# DB3100.net
KiCad netlist of a schematic drawn in Altium Designer
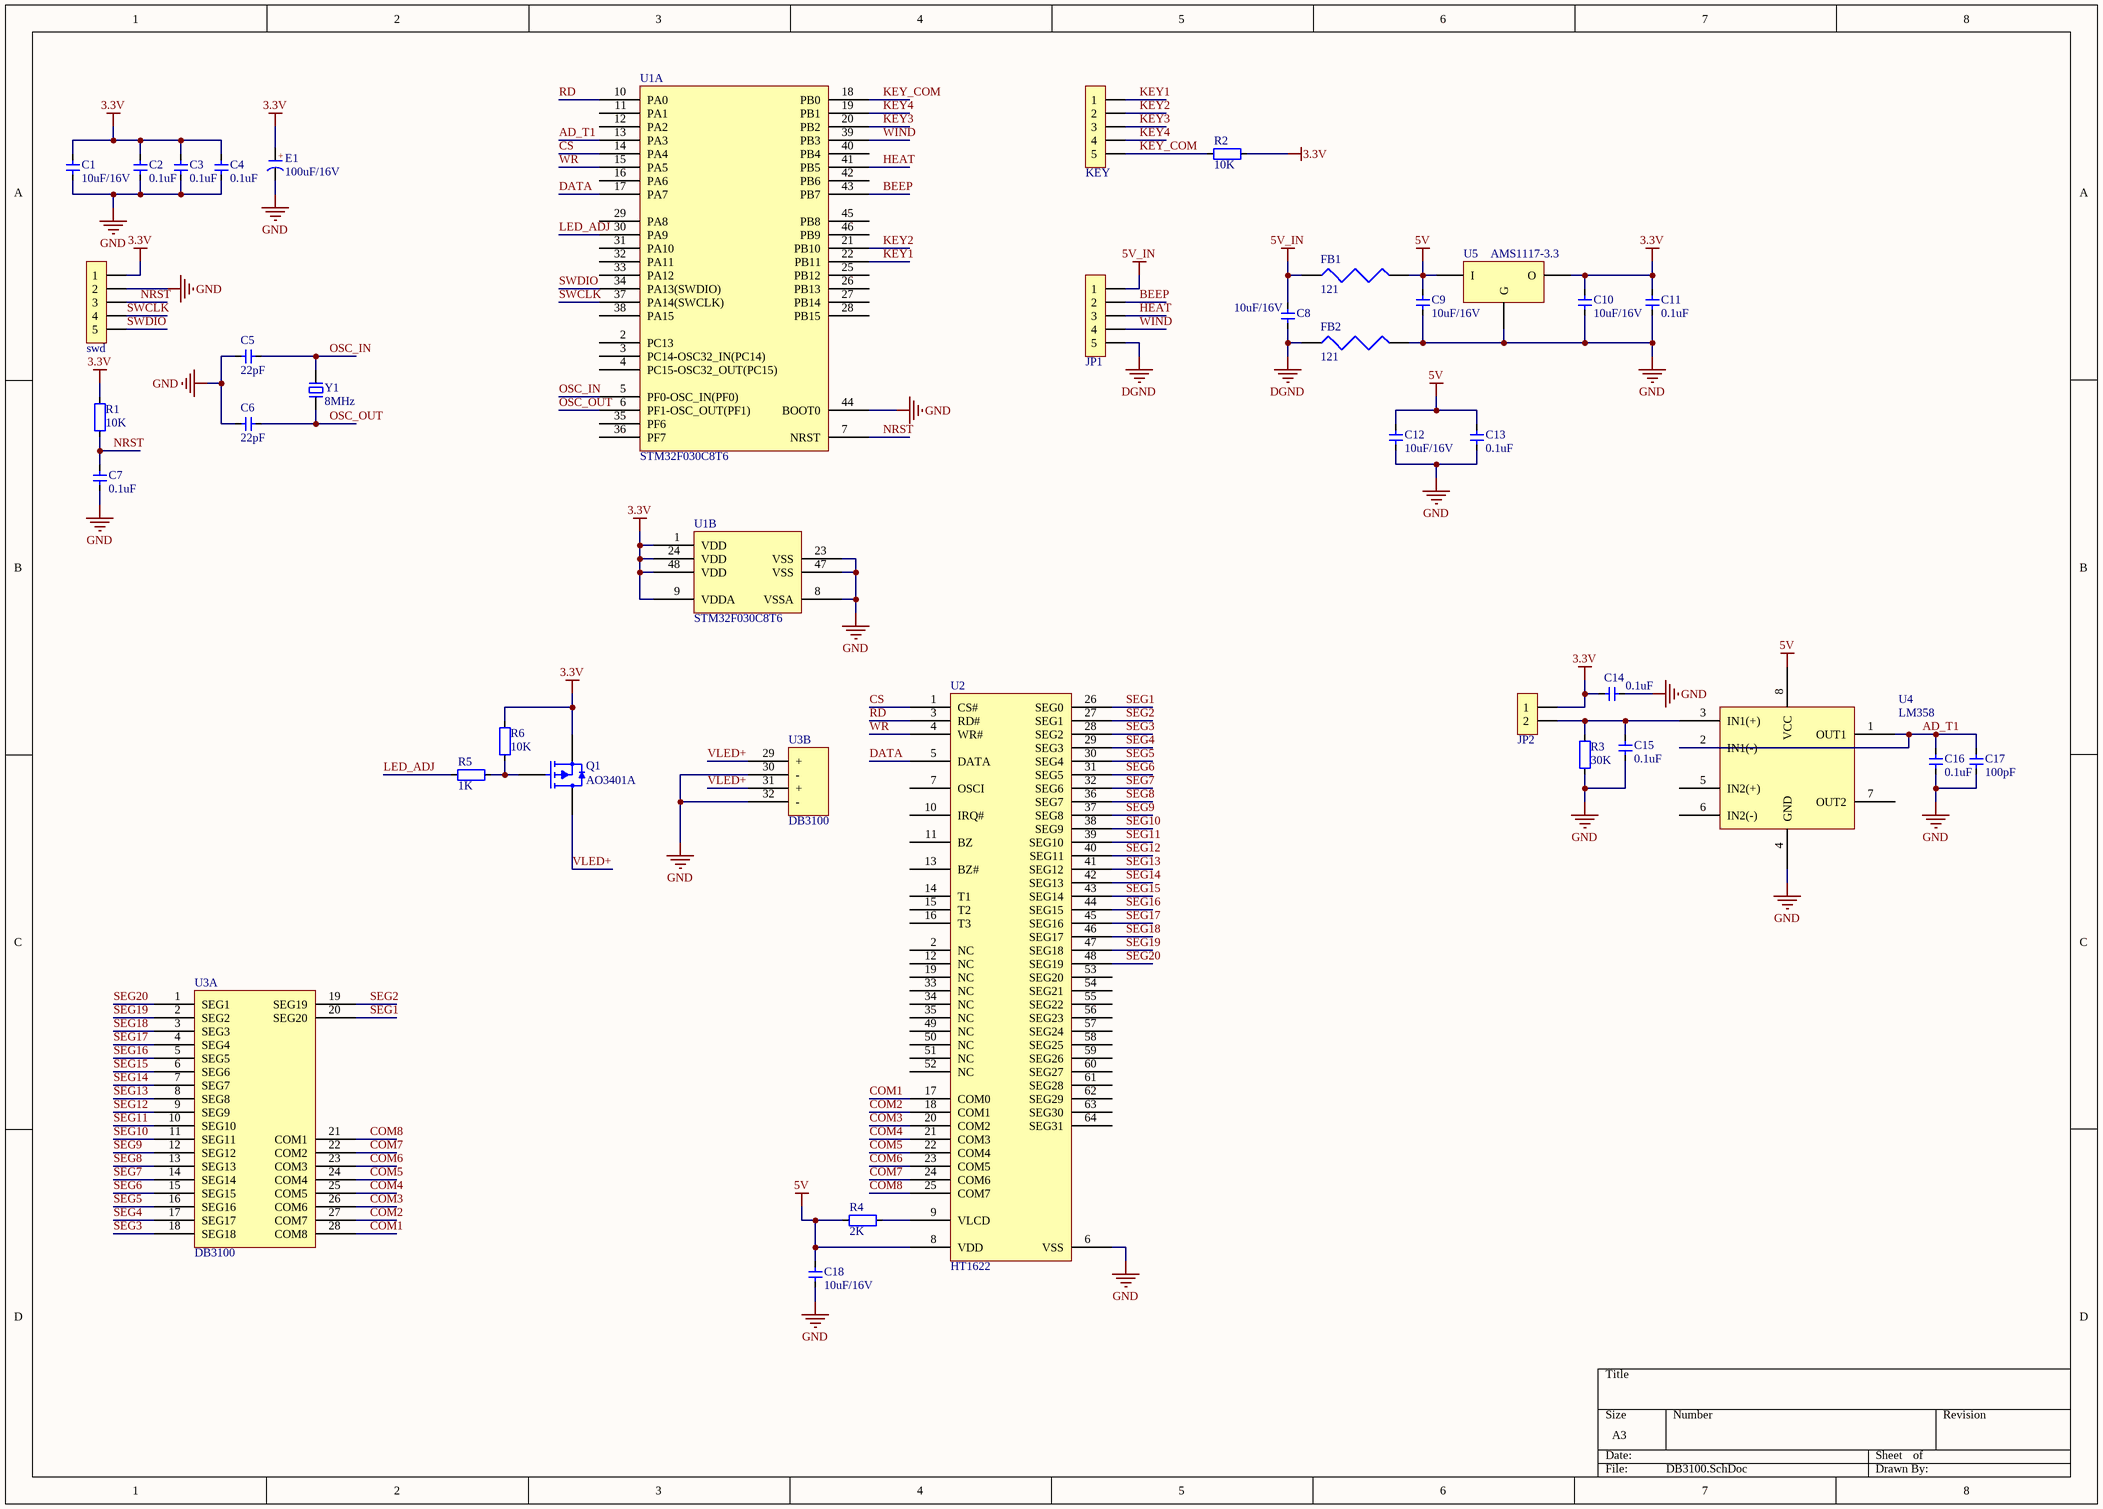
[diagram p0: DB3100.SchDoc]

(export (version "E")
  (design (tool "Eeschema 10.0.6"))
  (components
    (comp (ref "C1")
      (value "10uF/16V")
      (footprint "C 0805")
      (description "无极性贴片电容")
      (fields (field (name "版权归属") "源创客"))
      (libsource (lib "电容") (part "C"))
    )
    (comp (ref "C2")
      (value "0.1uF")
      (footprint "C 0603")
      (description "无极性贴片电容")
      (fields (field (name "版权归属") "源创客"))
      (libsource (lib "电容") (part "C"))
    )
    (comp (ref "C3")
      (value "0.1uF")
      (footprint "C 0603")
      (description "无极性贴片电容")
      (fields (field (name "版权归属") "源创客"))
      (libsource (lib "电容") (part "C"))
    )
    (comp (ref "C4")
      (value "0.1uF")
      (footprint "C 0603")
      (description "无极性贴片电容")
      (fields (field (name "版权归属") "源创客"))
      (libsource (lib "电容") (part "C"))
    )
    (comp (ref "C5")
      (value "22pF")
      (footprint "C 0603")
      (description "无极性贴片电容")
      (fields (field (name "版权归属") "源创客"))
      (libsource (lib "电容") (part "C"))
    )
    (comp (ref "C6")
      (value "22pF")
      (footprint "C 0603")
      (description "无极性贴片电容")
      (fields (field (name "版权归属") "源创客"))
      (libsource (lib "电容") (part "C"))
    )
    (comp (ref "C7")
      (value "0.1uF")
      (footprint "C 0603")
      (description "无极性贴片电容")
      (fields (field (name "版权归属") "源创客"))
      (libsource (lib "电容") (part "C"))
    )
    (comp (ref "C8")
      (value "10uF/16V")
      (footprint "C 0805")
      (description "无极性贴片电容")
      (fields (field (name "版权归属") "源创客"))
      (libsource (lib "电容") (part "C"))
    )
    (comp (ref "C9")
      (value "10uF/16V")
      (footprint "C 0805")
      (description "无极性贴片电容")
      (fields (field (name "版权归属") "源创客"))
      (libsource (lib "电容") (part "C"))
    )
    (comp (ref "C10")
      (value "10uF/16V")
      (footprint "C 0805")
      (description "无极性贴片电容")
      (fields (field (name "版权归属") "源创客"))
      (libsource (lib "电容") (part "C"))
    )
    (comp (ref "C11")
      (value "0.1uF")
      (footprint "C 0603")
      (description "无极性贴片电容")
      (fields (field (name "版权归属") "源创客"))
      (libsource (lib "电容") (part "C"))
    )
    (comp (ref "C12")
      (value "10uF/16V")
      (footprint "C 0805")
      (description "无极性贴片电容")
      (fields (field (name "版权归属") "源创客"))
      (libsource (lib "电容") (part "C"))
    )
    (comp (ref "C13")
      (value "0.1uF")
      (footprint "C 0603")
      (description "无极性贴片电容")
      (fields (field (name "版权归属") "源创客"))
      (libsource (lib "电容") (part "C"))
    )
    (comp (ref "C14")
      (value "0.1uF")
      (footprint "C 0603")
      (description "无极性贴片电容")
      (fields (field (name "版权归属") "源创客"))
      (libsource (lib "电容") (part "C"))
    )
    (comp (ref "C15")
      (value "0.1uF")
      (footprint "C 0603")
      (description "无极性贴片电容")
      (fields (field (name "版权归属") "源创客"))
      (libsource (lib "电容") (part "C"))
    )
    (comp (ref "C16")
      (value "0.1uF")
      (footprint "C 0603")
      (description "无极性贴片电容")
      (fields (field (name "版权归属") "源创客"))
      (libsource (lib "电容") (part "C"))
    )
    (comp (ref "C17")
      (value "100pF")
      (footprint "C 0603")
      (description "无极性贴片电容")
      (fields (field (name "版权归属") "源创客"))
      (libsource (lib "电容") (part "C"))
    )
    (comp (ref "C18")
      (value "10uF/16V")
      (footprint "C 0805")
      (description "无极性贴片电容")
      (fields (field (name "版权归属") "源创客"))
      (libsource (lib "电容") (part "C"))
    )
    (comp (ref "E1")
      (value "100uF/16V")
      (footprint "CM D(6.3*5.4)")
      (description "直插电解电容")
      (fields (field (name "版权归属") "源创客"))
      (libsource (lib "电容") (part "C-CAP"))
    )
    (comp (ref "FB1")
      (value "121")
      (footprint "L 0805")
      (description "磁珠")
      (libsource (lib "电感") (part "FB"))
    )
    (comp (ref "FB2")
      (value "121")
      (footprint "L 0805")
      (description "磁珠")
      (libsource (lib "电感") (part "FB"))
    )
    (comp (ref "JP1")
      (value "HDR-1X5")
      (footprint "XH2.54-5P")
      (description "5P接插件")
      (fields (field (name "版权归属") "源创客"))
      (libsource (lib "排针-排母") (part "Header 5"))
    )
    (comp (ref "JP2")
      (value "HDR-1X2")
      (footprint "XH2.54-2P")
      (description "2P接插件")
      (fields (field (name "版权归属") "源创客"))
      (libsource (lib "排针-排母") (part "Header 2"))
    )
    (comp (ref "KEY")
      (value "HDR-1X5")
      (footprint "HDR-1X5")
      (description "5P接插件")
      (fields (field (name "版权归属") "源创客"))
      (libsource (lib "排针-排母") (part "Header 5"))
    )
    (comp (ref "Q1")
      (value "AO3401A")
      (footprint "SOT23-3")
      (description "P-MOS")
      (libsource (lib "三极管") (part "AO3401A"))
    )
    (comp (ref "R1")
      (value "10K")
      (footprint "R 0603")
      (description "贴片电阻")
      (fields (field (name "版权归属") "源创客"))
      (libsource (lib "") (part "R_1"))
    )
    (comp (ref "R2")
      (value "10K")
      (footprint "R 0603")
      (description "贴片电阻")
      (fields (field (name "版权归属") "源创客"))
      (libsource (lib "电阻") (part "R"))
    )
    (comp (ref "R3")
      (value "30K")
      (footprint "R 0603")
      (description "贴片电阻")
      (fields (field (name "版权归属") "源创客"))
      (libsource (lib "") (part "R_1"))
    )
    (comp (ref "R4")
      (value "2K")
      (footprint "R 0603")
      (description "贴片电阻")
      (fields (field (name "版权归属") "源创客"))
      (libsource (lib "电阻") (part "R"))
    )
    (comp (ref "R5")
      (value "1K")
      (footprint "R 0603")
      (description "贴片电阻")
      (fields (field (name "版权归属") "源创客"))
      (libsource (lib "电阻") (part "R"))
    )
    (comp (ref "R6")
      (value "10K")
      (footprint "R 0603")
      (description "贴片电阻")
      (fields (field (name "版权归属") "源创客"))
      (libsource (lib "") (part "R_1"))
    )
    (comp (ref "swd")
      (value "HDR-1X5")
      (footprint "XH2.54-5P")
      (description "5P接插件")
      (fields (field (name "版权归属") "源创客"))
      (libsource (lib "排针-排母") (part "Header 5"))
    )
    (comp (ref "U1")
      (value "STM32F030C8T6")
      (footprint "STM32F030C8T6")
      (libsource (lib "STM32系列单片机") (part "STM32F030C8T6"))
    )
    (comp (ref "U2")
      (value "HT1622")
      (footprint "HT1622")
      (description "LCD驱动，64引脚")
      (libsource (lib "显示芯片") (part "HT1622"))
    )
    (comp (ref "U3")
      (value "DB3100")
      (footprint "DB3100")
      (description "DB3100的屏幕")
      (libsource (lib "显示屏幕") (part "DB3100"))
    )
    (comp (ref "U4")
      (value "LM358")
      (footprint "LM358")
      (description "LM358是由两个独立的高增益运算放大器组成")
      (libsource (lib "常用芯片") (part "LM358"))
    )
    (comp (ref "U5")
      (value "AMS1117-3.3")
      (footprint "AMS1117-3.3")
      (description "转3.3V电压")
      (libsource (lib "变压器") (part "AMS1117-3.3"))
    )
    (comp (ref "Y1")
      (value "8MHz")
      (footprint "XTAL-49S SMD")
      (description "2脚晶振")
      (fields (field (name "版权归属") "源创客"))
      (libsource (lib "晶振") (part "XTAL-2"))
    )
  )
  (nets
    (net (code "1") (name "/AD_T1") (class "Default")
      (node (ref "C16") (pin "2") (pinfunction "2_2") (pintype "passive"))
      (node (ref "C17") (pin "2") (pinfunction "2_2") (pintype "passive"))
      (node (ref "U1") (pin "13") (pinfunction "PA3_13") (pintype "passive"))
      (node (ref "U4") (pin "1") (pinfunction "OUT1_1") (pintype "passive"))
      (node (ref "U4") (pin "2") (pinfunction "IN1(-)_2") (pintype "passive"))
    )
    (net (code "2") (name "/BEEP") (class "Default")
      (node (ref "JP1") (pin "2") (pinfunction "2_2") (pintype "passive"))
      (node (ref "U1") (pin "43") (pinfunction "PB7_43") (pintype "passive"))
    )
    (net (code "3") (name "/COM1") (class "Default")
      (node (ref "U2") (pin "17") (pinfunction "COM0_17") (pintype "passive"))
      (node (ref "U3") (pin "28") (pinfunction "COM8_28") (pintype "passive"))
    )
    (net (code "4") (name "/COM2") (class "Default")
      (node (ref "U2") (pin "18") (pinfunction "COM1_18") (pintype "passive"))
      (node (ref "U3") (pin "27") (pinfunction "COM7_27") (pintype "passive"))
    )
    (net (code "5") (name "/COM3") (class "Default")
      (node (ref "U2") (pin "20") (pinfunction "COM2_20") (pintype "passive"))
      (node (ref "U3") (pin "26") (pinfunction "COM6_26") (pintype "passive"))
    )
    (net (code "6") (name "/COM4") (class "Default")
      (node (ref "U2") (pin "21") (pinfunction "COM3_21") (pintype "passive"))
      (node (ref "U3") (pin "25") (pinfunction "COM5_25") (pintype "passive"))
    )
    (net (code "7") (name "/COM5") (class "Default")
      (node (ref "U2") (pin "22") (pinfunction "COM4_22") (pintype "passive"))
      (node (ref "U3") (pin "24") (pinfunction "COM4_24") (pintype "passive"))
    )
    (net (code "8") (name "/COM6") (class "Default")
      (node (ref "U2") (pin "23") (pinfunction "COM5_23") (pintype "passive"))
      (node (ref "U3") (pin "23") (pinfunction "COM3_23") (pintype "passive"))
    )
    (net (code "9") (name "/COM7") (class "Default")
      (node (ref "U2") (pin "24") (pinfunction "COM6_24") (pintype "passive"))
      (node (ref "U3") (pin "22") (pinfunction "COM2_22") (pintype "passive"))
    )
    (net (code "10") (name "/COM8") (class "Default")
      (node (ref "U2") (pin "25") (pinfunction "COM7_25") (pintype "passive"))
      (node (ref "U3") (pin "21") (pinfunction "COM1_21") (pintype "passive"))
    )
    (net (code "11") (name "/CS") (class "Default")
      (node (ref "U1") (pin "14") (pinfunction "PA4_14") (pintype "passive"))
      (node (ref "U2") (pin "1") (pinfunction "CS#_1") (pintype "passive"))
    )
    (net (code "12") (name "/DATA") (class "Default")
      (node (ref "U1") (pin "17") (pinfunction "PA7_17") (pintype "passive"))
      (node (ref "U2") (pin "5") (pinfunction "DATA_5") (pintype "passive"))
    )
    (net (code "13") (name "/HEAT") (class "Default")
      (node (ref "JP1") (pin "3") (pinfunction "3_3") (pintype "passive"))
      (node (ref "U1") (pin "41") (pinfunction "PB5_41") (pintype "passive"))
    )
    (net (code "14") (name "/KEY1") (class "Default")
      (node (ref "KEY") (pin "1") (pinfunction "1_1") (pintype "passive"))
      (node (ref "U1") (pin "22") (pinfunction "PB11_22") (pintype "passive"))
    )
    (net (code "15") (name "/KEY2") (class "Default")
      (node (ref "KEY") (pin "2") (pinfunction "2_2") (pintype "passive"))
      (node (ref "U1") (pin "21") (pinfunction "PB10_21") (pintype "passive"))
    )
    (net (code "16") (name "/KEY3") (class "Default")
      (node (ref "KEY") (pin "3") (pinfunction "3_3") (pintype "passive"))
      (node (ref "U1") (pin "20") (pinfunction "PB2_20") (pintype "passive"))
    )
    (net (code "17") (name "/KEY4") (class "Default")
      (node (ref "KEY") (pin "4") (pinfunction "4_4") (pintype "passive"))
      (node (ref "U1") (pin "19") (pinfunction "PB1_19") (pintype "passive"))
    )
    (net (code "18") (name "/KEY_COM") (class "Default")
      (node (ref "KEY") (pin "5") (pinfunction "5_5") (pintype "passive"))
      (node (ref "R2") (pin "1") (pinfunction "1_1") (pintype "passive"))
      (node (ref "U1") (pin "18") (pinfunction "PB0_18") (pintype "passive"))
    )
    (net (code "19") (name "/LED_ADJ") (class "Default")
      (node (ref "R5") (pin "1") (pinfunction "1_1") (pintype "passive"))
      (node (ref "U1") (pin "30") (pinfunction "PA9_30") (pintype "passive"))
    )
    (net (code "20") (name "/NRST") (class "Default")
      (node (ref "C7") (pin "2") (pinfunction "2_2") (pintype "passive"))
      (node (ref "R1") (pin "1") (pinfunction "1_1") (pintype "passive"))
      (node (ref "U1") (pin "7") (pinfunction "NRST_7") (pintype "passive"))
      (node (ref "swd") (pin "3") (pinfunction "3_3") (pintype "passive"))
    )
    (net (code "21") (name "/OSC_IN") (class "Default")
      (node (ref "C5") (pin "2") (pinfunction "2_2") (pintype "passive"))
      (node (ref "U1") (pin "5") (pinfunction "PF0-OSC_IN(PF0)_5") (pintype "passive"))
      (node (ref "Y1") (pin "2") (pinfunction "2_2") (pintype "passive"))
    )
    (net (code "22") (name "/OSC_OUT") (class "Default")
      (node (ref "C6") (pin "2") (pinfunction "2_2") (pintype "passive"))
      (node (ref "U1") (pin "6") (pinfunction "PF1-OSC_OUT(PF1)_6") (pintype "passive"))
      (node (ref "Y1") (pin "1") (pinfunction "1_1") (pintype "passive"))
    )
    (net (code "23") (name "/RD") (class "Default")
      (node (ref "U1") (pin "10") (pinfunction "PA0_10") (pintype "passive"))
      (node (ref "U2") (pin "3") (pinfunction "RD#_3") (pintype "passive"))
    )
    (net (code "24") (name "/SEG1") (class "Default")
      (node (ref "U2") (pin "26") (pinfunction "SEG0_26") (pintype "passive"))
      (node (ref "U3") (pin "20") (pinfunction "SEG20_20") (pintype "passive"))
    )
    (net (code "25") (name "/SEG2") (class "Default")
      (node (ref "U2") (pin "27") (pinfunction "SEG1_27") (pintype "passive"))
      (node (ref "U3") (pin "19") (pinfunction "SEG19_19") (pintype "passive"))
    )
    (net (code "26") (name "/SEG3") (class "Default")
      (node (ref "U2") (pin "28") (pinfunction "SEG2_28") (pintype "passive"))
      (node (ref "U3") (pin "18") (pinfunction "SEG18_18") (pintype "passive"))
    )
    (net (code "27") (name "/SEG4") (class "Default")
      (node (ref "U2") (pin "29") (pinfunction "SEG3_29") (pintype "passive"))
      (node (ref "U3") (pin "17") (pinfunction "SEG17_17") (pintype "passive"))
    )
    (net (code "28") (name "/SEG5") (class "Default")
      (node (ref "U2") (pin "30") (pinfunction "SEG4_30") (pintype "passive"))
      (node (ref "U3") (pin "16") (pinfunction "SEG16_16") (pintype "passive"))
    )
    (net (code "29") (name "/SEG6") (class "Default")
      (node (ref "U2") (pin "31") (pinfunction "SEG5_31") (pintype "passive"))
      (node (ref "U3") (pin "15") (pinfunction "SEG15_15") (pintype "passive"))
    )
    (net (code "30") (name "/SEG7") (class "Default")
      (node (ref "U2") (pin "32") (pinfunction "SEG6_32") (pintype "passive"))
      (node (ref "U3") (pin "14") (pinfunction "SEG14_14") (pintype "passive"))
    )
    (net (code "31") (name "/SEG8") (class "Default")
      (node (ref "U2") (pin "36") (pinfunction "SEG7_36") (pintype "passive"))
      (node (ref "U3") (pin "13") (pinfunction "SEG13_13") (pintype "passive"))
    )
    (net (code "32") (name "/SEG9") (class "Default")
      (node (ref "U2") (pin "37") (pinfunction "SEG8_37") (pintype "passive"))
      (node (ref "U3") (pin "12") (pinfunction "SEG12_12") (pintype "passive"))
    )
    (net (code "33") (name "/SEG10") (class "Default")
      (node (ref "U2") (pin "38") (pinfunction "SEG9_38") (pintype "passive"))
      (node (ref "U3") (pin "11") (pinfunction "SEG11_11") (pintype "passive"))
    )
    (net (code "34") (name "/SEG11") (class "Default")
      (node (ref "U2") (pin "39") (pinfunction "SEG10_39") (pintype "passive"))
      (node (ref "U3") (pin "10") (pinfunction "SEG10_10") (pintype "passive"))
    )
    (net (code "35") (name "/SEG12") (class "Default")
      (node (ref "U2") (pin "40") (pinfunction "SEG11_40") (pintype "passive"))
      (node (ref "U3") (pin "9") (pinfunction "SEG9_9") (pintype "passive"))
    )
    (net (code "36") (name "/SEG13") (class "Default")
      (node (ref "U2") (pin "41") (pinfunction "SEG12_41") (pintype "passive"))
      (node (ref "U3") (pin "8") (pinfunction "SEG8_8") (pintype "passive"))
    )
    (net (code "37") (name "/SEG14") (class "Default")
      (node (ref "U2") (pin "42") (pinfunction "SEG13_42") (pintype "passive"))
      (node (ref "U3") (pin "7") (pinfunction "SEG7_7") (pintype "passive"))
    )
    (net (code "38") (name "/SEG15") (class "Default")
      (node (ref "U2") (pin "43") (pinfunction "SEG14_43") (pintype "passive"))
      (node (ref "U3") (pin "6") (pinfunction "SEG6_6") (pintype "passive"))
    )
    (net (code "39") (name "/SEG16") (class "Default")
      (node (ref "U2") (pin "44") (pinfunction "SEG15_44") (pintype "passive"))
      (node (ref "U3") (pin "5") (pinfunction "SEG5_5") (pintype "passive"))
    )
    (net (code "40") (name "/SEG17") (class "Default")
      (node (ref "U2") (pin "45") (pinfunction "SEG16_45") (pintype "passive"))
      (node (ref "U3") (pin "4") (pinfunction "SEG4_4") (pintype "passive"))
    )
    (net (code "41") (name "/SEG18") (class "Default")
      (node (ref "U2") (pin "46") (pinfunction "SEG17_46") (pintype "passive"))
      (node (ref "U3") (pin "3") (pinfunction "SEG3_3") (pintype "passive"))
    )
    (net (code "42") (name "/SEG19") (class "Default")
      (node (ref "U2") (pin "47") (pinfunction "SEG18_47") (pintype "passive"))
      (node (ref "U3") (pin "2") (pinfunction "SEG2_2") (pintype "passive"))
    )
    (net (code "43") (name "/SEG20") (class "Default")
      (node (ref "U2") (pin "48") (pinfunction "SEG19_48") (pintype "passive"))
      (node (ref "U3") (pin "1") (pinfunction "SEG1_1") (pintype "passive"))
    )
    (net (code "44") (name "/SWCLK") (class "Default")
      (node (ref "U1") (pin "37") (pinfunction "PA14(SWCLK)_37") (pintype "passive"))
      (node (ref "swd") (pin "4") (pinfunction "4_4") (pintype "passive"))
    )
    (net (code "45") (name "/SWDIO") (class "Default")
      (node (ref "U1") (pin "34") (pinfunction "PA13(SWDIO)_34") (pintype "passive"))
      (node (ref "swd") (pin "5") (pinfunction "5_5") (pintype "passive"))
    )
    (net (code "46") (name "/VLED+") (class "Default")
      (node (ref "Q1") (pin "3") (pinfunction "D_3") (pintype "passive"))
      (node (ref "U3") (pin "29") (pinfunction "+_29") (pintype "passive"))
      (node (ref "U3") (pin "31") (pinfunction "+_31") (pintype "passive"))
    )
    (net (code "47") (name "/WIND") (class "Default")
      (node (ref "JP1") (pin "4") (pinfunction "4_4") (pintype "passive"))
      (node (ref "U1") (pin "39") (pinfunction "PB3_39") (pintype "passive"))
    )
    (net (code "48") (name "/WR") (class "Default")
      (node (ref "U1") (pin "15") (pinfunction "PA5_15") (pintype "passive"))
      (node (ref "U2") (pin "4") (pinfunction "WR#_4") (pintype "passive"))
    )
    (net (code "49") (name "3.3V") (class "Default")
      (node (ref "C1") (pin "2") (pinfunction "2_2") (pintype "passive"))
      (node (ref "C10") (pin "2") (pinfunction "2_2") (pintype "passive"))
      (node (ref "C11") (pin "2") (pinfunction "2_2") (pintype "passive"))
      (node (ref "C14") (pin "1") (pinfunction "1_1") (pintype "passive"))
      (node (ref "C2") (pin "2") (pinfunction "2_2") (pintype "passive"))
      (node (ref "C3") (pin "2") (pinfunction "2_2") (pintype "passive"))
      (node (ref "C4") (pin "2") (pinfunction "2_2") (pintype "passive"))
      (node (ref "E1") (pin "1") (pinfunction "A_1") (pintype "passive"))
      (node (ref "JP2") (pin "1") (pinfunction "1_1") (pintype "passive"))
      (node (ref "Q1") (pin "2") (pinfunction "S_2") (pintype "passive"))
      (node (ref "R1") (pin "2") (pinfunction "2_2") (pintype "passive"))
      (node (ref "R2") (pin "2") (pinfunction "2_2") (pintype "passive"))
      (node (ref "R6") (pin "2") (pinfunction "2_2") (pintype "passive"))
      (node (ref "U1") (pin "1") (pinfunction "VDD_1") (pintype "passive"))
      (node (ref "U1") (pin "24") (pinfunction "VDD_24") (pintype "passive"))
      (node (ref "U1") (pin "48") (pinfunction "VDD_48") (pintype "passive"))
      (node (ref "U1") (pin "9") (pinfunction "VDDA_9") (pintype "passive"))
      (node (ref "U5") (pin "2") (pinfunction "O_2") (pintype "passive"))
      (node (ref "swd") (pin "1") (pinfunction "1_1") (pintype "passive"))
    )
    (net (code "50") (name "5V") (class "Default")
      (node (ref "C12") (pin "2") (pinfunction "2_2") (pintype "passive"))
      (node (ref "C13") (pin "2") (pinfunction "2_2") (pintype "passive"))
      (node (ref "C18") (pin "2") (pinfunction "2_2") (pintype "passive"))
      (node (ref "C9") (pin "2") (pinfunction "2_2") (pintype "passive"))
      (node (ref "FB1") (pin "2") (pinfunction "2_2") (pintype "passive"))
      (node (ref "R4") (pin "1") (pinfunction "1_1") (pintype "passive"))
      (node (ref "U2") (pin "8") (pinfunction "VDD_8") (pintype "passive"))
      (node (ref "U4") (pin "8") (pinfunction "VCC_8") (pintype "passive"))
      (node (ref "U5") (pin "3") (pinfunction "I_3") (pintype "passive"))
    )
    (net (code "51") (name "5V_IN") (class "Default")
      (node (ref "C8") (pin "2") (pinfunction "2_2") (pintype "passive"))
      (node (ref "FB1") (pin "1") (pinfunction "1_1") (pintype "passive"))
      (node (ref "JP1") (pin "1") (pinfunction "1_1") (pintype "passive"))
    )
    (net (code "52") (name "DGND") (class "Default")
      (node (ref "C8") (pin "1") (pinfunction "1_1") (pintype "passive"))
      (node (ref "FB2") (pin "1") (pinfunction "1_1") (pintype "passive"))
      (node (ref "JP1") (pin "5") (pinfunction "5_5") (pintype "passive"))
    )
    (net (code "53") (name "GND") (class "Default")
      (node (ref "C1") (pin "1") (pinfunction "1_1") (pintype "passive"))
      (node (ref "C10") (pin "1") (pinfunction "1_1") (pintype "passive"))
      (node (ref "C11") (pin "1") (pinfunction "1_1") (pintype "passive"))
      (node (ref "C12") (pin "1") (pinfunction "1_1") (pintype "passive"))
      (node (ref "C13") (pin "1") (pinfunction "1_1") (pintype "passive"))
      (node (ref "C14") (pin "2") (pinfunction "2_2") (pintype "passive"))
      (node (ref "C15") (pin "1") (pinfunction "1_1") (pintype "passive"))
      (node (ref "C16") (pin "1") (pinfunction "1_1") (pintype "passive"))
      (node (ref "C17") (pin "1") (pinfunction "1_1") (pintype "passive"))
      (node (ref "C18") (pin "1") (pinfunction "1_1") (pintype "passive"))
      (node (ref "C2") (pin "1") (pinfunction "1_1") (pintype "passive"))
      (node (ref "C3") (pin "1") (pinfunction "1_1") (pintype "passive"))
      (node (ref "C4") (pin "1") (pinfunction "1_1") (pintype "passive"))
      (node (ref "C5") (pin "1") (pinfunction "1_1") (pintype "passive"))
      (node (ref "C6") (pin "1") (pinfunction "1_1") (pintype "passive"))
      (node (ref "C7") (pin "1") (pinfunction "1_1") (pintype "passive"))
      (node (ref "C9") (pin "1") (pinfunction "1_1") (pintype "passive"))
      (node (ref "E1") (pin "2") (pinfunction "K_2") (pintype "passive"))
      (node (ref "FB2") (pin "2") (pinfunction "2_2") (pintype "passive"))
      (node (ref "R3") (pin "1") (pinfunction "1_1") (pintype "passive"))
      (node (ref "U1") (pin "23") (pinfunction "VSS_23") (pintype "passive"))
      (node (ref "U1") (pin "44") (pinfunction "BOOT0_44") (pintype "passive"))
      (node (ref "U1") (pin "47") (pinfunction "VSS_47") (pintype "passive"))
      (node (ref "U1") (pin "8") (pinfunction "VSSA_8") (pintype "passive"))
      (node (ref "U2") (pin "6") (pinfunction "VSS_6") (pintype "passive"))
      (node (ref "U3") (pin "30") (pinfunction "-_30") (pintype "passive"))
      (node (ref "U3") (pin "32") (pinfunction "-_32") (pintype "passive"))
      (node (ref "U4") (pin "4") (pinfunction "GND_4") (pintype "passive"))
      (node (ref "U5") (pin "1") (pinfunction "G_1") (pintype "passive"))
      (node (ref "swd") (pin "2") (pinfunction "2_2") (pintype "passive"))
    )
    (net (code "54") (name "Net-(Q1-G)") (class "Default")
      (node (ref "Q1") (pin "1") (pinfunction "G_1") (pintype "passive"))
      (node (ref "R5") (pin "2") (pinfunction "2_2") (pintype "passive"))
      (node (ref "R6") (pin "1") (pinfunction "1_1") (pintype "passive"))
    )
    (net (code "55") (name "Net-(U2-VLCD)") (class "Default")
      (node (ref "R4") (pin "2") (pinfunction "2_2") (pintype "passive"))
      (node (ref "U2") (pin "9") (pinfunction "VLCD_9") (pintype "passive"))
    )
    (net (code "56") (name "Net-(U4-IN1(+))") (class "Default")
      (node (ref "C15") (pin "2") (pinfunction "2_2") (pintype "passive"))
      (node (ref "JP2") (pin "2") (pinfunction "2_2") (pintype "passive"))
      (node (ref "R3") (pin "2") (pinfunction "2_2") (pintype "passive"))
      (node (ref "U4") (pin "3") (pinfunction "IN1(+)_3") (pintype "passive"))
    )
    (net (code "57") (name "unconnected-(U1A-PA1-Pad11)") (class "Default")
      (node (ref "U1") (pin "11") (pinfunction "PA1_11") (pintype "passive"))
    )
    (net (code "58") (name "unconnected-(U1A-PA2-Pad12)") (class "Default")
      (node (ref "U1") (pin "12") (pinfunction "PA2_12") (pintype "passive"))
    )
    (net (code "59") (name "unconnected-(U1A-PA6-Pad16)") (class "Default")
      (node (ref "U1") (pin "16") (pinfunction "PA6_16") (pintype "passive"))
    )
    (net (code "60") (name "unconnected-(U1A-PA8-Pad29)") (class "Default")
      (node (ref "U1") (pin "29") (pinfunction "PA8_29") (pintype "passive"))
    )
    (net (code "61") (name "unconnected-(U1A-PA10-Pad31)") (class "Default")
      (node (ref "U1") (pin "31") (pinfunction "PA10_31") (pintype "passive"))
    )
    (net (code "62") (name "unconnected-(U1A-PA11-Pad32)") (class "Default")
      (node (ref "U1") (pin "32") (pinfunction "PA11_32") (pintype "passive"))
    )
    (net (code "63") (name "unconnected-(U1A-PA12-Pad33)") (class "Default")
      (node (ref "U1") (pin "33") (pinfunction "PA12_33") (pintype "passive"))
    )
    (net (code "64") (name "unconnected-(U1A-PA15-Pad38)") (class "Default")
      (node (ref "U1") (pin "38") (pinfunction "PA15_38") (pintype "passive"))
    )
    (net (code "65") (name "unconnected-(U1A-PB4-Pad40)") (class "Default")
      (node (ref "U1") (pin "40") (pinfunction "PB4_40") (pintype "passive"))
    )
    (net (code "66") (name "unconnected-(U1A-PB6-Pad42)") (class "Default")
      (node (ref "U1") (pin "42") (pinfunction "PB6_42") (pintype "passive"))
    )
    (net (code "67") (name "unconnected-(U1A-PB8-Pad45)") (class "Default")
      (node (ref "U1") (pin "45") (pinfunction "PB8_45") (pintype "passive"))
    )
    (net (code "68") (name "unconnected-(U1A-PB9-Pad46)") (class "Default")
      (node (ref "U1") (pin "46") (pinfunction "PB9_46") (pintype "passive"))
    )
    (net (code "69") (name "unconnected-(U1A-PB12-Pad25)") (class "Default")
      (node (ref "U1") (pin "25") (pinfunction "PB12_25") (pintype "passive"))
    )
    (net (code "70") (name "unconnected-(U1A-PB13-Pad26)") (class "Default")
      (node (ref "U1") (pin "26") (pinfunction "PB13_26") (pintype "passive"))
    )
    (net (code "71") (name "unconnected-(U1A-PB14-Pad27)") (class "Default")
      (node (ref "U1") (pin "27") (pinfunction "PB14_27") (pintype "passive"))
    )
    (net (code "72") (name "unconnected-(U1A-PB15-Pad28)") (class "Default")
      (node (ref "U1") (pin "28") (pinfunction "PB15_28") (pintype "passive"))
    )
    (net (code "73") (name "unconnected-(U1A-PC13-Pad2)") (class "Default")
      (node (ref "U1") (pin "2") (pinfunction "PC13_2") (pintype "passive"))
    )
    (net (code "74") (name "unconnected-(U1A-PC14-OSC32_IN(PC14)-Pad3)") (class "Default")
      (node (ref "U1") (pin "3") (pinfunction "PC14-OSC32_IN(PC14)_3") (pintype "passive"))
    )
    (net (code "75") (name "unconnected-(U1A-PC15-OSC32_OUT(PC15)-Pad4)") (class "Default")
      (node (ref "U1") (pin "4") (pinfunction "PC15-OSC32_OUT(PC15)_4") (pintype "passive"))
    )
    (net (code "76") (name "unconnected-(U1A-PF6-Pad35)") (class "Default")
      (node (ref "U1") (pin "35") (pinfunction "PF6_35") (pintype "passive"))
    )
    (net (code "77") (name "unconnected-(U1A-PF7-Pad36)") (class "Default")
      (node (ref "U1") (pin "36") (pinfunction "PF7_36") (pintype "passive"))
    )
    (net (code "78") (name "unconnected-(U2-BZ#-Pad13)") (class "Default")
      (node (ref "U2") (pin "13") (pinfunction "BZ#_13") (pintype "passive"))
    )
    (net (code "79") (name "unconnected-(U2-BZ-Pad11)") (class "Default")
      (node (ref "U2") (pin "11") (pinfunction "BZ_11") (pintype "passive"))
    )
    (net (code "80") (name "unconnected-(U2-IRQ#-Pad10)") (class "Default")
      (node (ref "U2") (pin "10") (pinfunction "IRQ#_10") (pintype "passive"))
    )
    (net (code "81") (name "unconnected-(U2-NC-Pad2)") (class "Default")
      (node (ref "U2") (pin "2") (pinfunction "NC_2") (pintype "passive"))
    )
    (net (code "82") (name "unconnected-(U2-NC-Pad12)") (class "Default")
      (node (ref "U2") (pin "12") (pinfunction "NC_12") (pintype "passive"))
    )
    (net (code "83") (name "unconnected-(U2-NC-Pad19)") (class "Default")
      (node (ref "U2") (pin "19") (pinfunction "NC_19") (pintype "passive"))
    )
    (net (code "84") (name "unconnected-(U2-NC-Pad33)") (class "Default")
      (node (ref "U2") (pin "33") (pinfunction "NC_33") (pintype "passive"))
    )
    (net (code "85") (name "unconnected-(U2-NC-Pad34)") (class "Default")
      (node (ref "U2") (pin "34") (pinfunction "NC_34") (pintype "passive"))
    )
    (net (code "86") (name "unconnected-(U2-NC-Pad35)") (class "Default")
      (node (ref "U2") (pin "35") (pinfunction "NC_35") (pintype "passive"))
    )
    (net (code "87") (name "unconnected-(U2-NC-Pad49)") (class "Default")
      (node (ref "U2") (pin "49") (pinfunction "NC_49") (pintype "passive"))
    )
    (net (code "88") (name "unconnected-(U2-NC-Pad50)") (class "Default")
      (node (ref "U2") (pin "50") (pinfunction "NC_50") (pintype "passive"))
    )
    (net (code "89") (name "unconnected-(U2-NC-Pad51)") (class "Default")
      (node (ref "U2") (pin "51") (pinfunction "NC_51") (pintype "passive"))
    )
    (net (code "90") (name "unconnected-(U2-NC-Pad52)") (class "Default")
      (node (ref "U2") (pin "52") (pinfunction "NC_52") (pintype "passive"))
    )
    (net (code "91") (name "unconnected-(U2-OSCI-Pad7)") (class "Default")
      (node (ref "U2") (pin "7") (pinfunction "OSCI_7") (pintype "passive"))
    )
    (net (code "92") (name "unconnected-(U2-SEG20-Pad53)") (class "Default")
      (node (ref "U2") (pin "53") (pinfunction "SEG20_53") (pintype "passive"))
    )
    (net (code "93") (name "unconnected-(U2-SEG21-Pad54)") (class "Default")
      (node (ref "U2") (pin "54") (pinfunction "SEG21_54") (pintype "passive"))
    )
    (net (code "94") (name "unconnected-(U2-SEG22-Pad55)") (class "Default")
      (node (ref "U2") (pin "55") (pinfunction "SEG22_55") (pintype "passive"))
    )
    (net (code "95") (name "unconnected-(U2-SEG23-Pad56)") (class "Default")
      (node (ref "U2") (pin "56") (pinfunction "SEG23_56") (pintype "passive"))
    )
    (net (code "96") (name "unconnected-(U2-SEG24-Pad57)") (class "Default")
      (node (ref "U2") (pin "57") (pinfunction "SEG24_57") (pintype "passive"))
    )
    (net (code "97") (name "unconnected-(U2-SEG25-Pad58)") (class "Default")
      (node (ref "U2") (pin "58") (pinfunction "SEG25_58") (pintype "passive"))
    )
    (net (code "98") (name "unconnected-(U2-SEG26-Pad59)") (class "Default")
      (node (ref "U2") (pin "59") (pinfunction "SEG26_59") (pintype "passive"))
    )
    (net (code "99") (name "unconnected-(U2-SEG27-Pad60)") (class "Default")
      (node (ref "U2") (pin "60") (pinfunction "SEG27_60") (pintype "passive"))
    )
    (net (code "100") (name "unconnected-(U2-SEG28-Pad61)") (class "Default")
      (node (ref "U2") (pin "61") (pinfunction "SEG28_61") (pintype "passive"))
    )
    (net (code "101") (name "unconnected-(U2-SEG29-Pad62)") (class "Default")
      (node (ref "U2") (pin "62") (pinfunction "SEG29_62") (pintype "passive"))
    )
    (net (code "102") (name "unconnected-(U2-SEG30-Pad63)") (class "Default")
      (node (ref "U2") (pin "63") (pinfunction "SEG30_63") (pintype "passive"))
    )
    (net (code "103") (name "unconnected-(U2-SEG31-Pad64)") (class "Default")
      (node (ref "U2") (pin "64") (pinfunction "SEG31_64") (pintype "passive"))
    )
    (net (code "104") (name "unconnected-(U2-T1-Pad14)") (class "Default")
      (node (ref "U2") (pin "14") (pinfunction "T1_14") (pintype "passive"))
    )
    (net (code "105") (name "unconnected-(U2-T2-Pad15)") (class "Default")
      (node (ref "U2") (pin "15") (pinfunction "T2_15") (pintype "passive"))
    )
    (net (code "106") (name "unconnected-(U2-T3-Pad16)") (class "Default")
      (node (ref "U2") (pin "16") (pinfunction "T3_16") (pintype "passive"))
    )
    (net (code "107") (name "unconnected-(U4-IN2(+)-Pad5)") (class "Default")
      (node (ref "U4") (pin "5") (pinfunction "IN2(+)_5") (pintype "passive"))
    )
    (net (code "108") (name "unconnected-(U4-IN2(-)-Pad6)") (class "Default")
      (node (ref "U4") (pin "6") (pinfunction "IN2(-)_6") (pintype "passive"))
    )
    (net (code "109") (name "unconnected-(U4-OUT2-Pad7)") (class "Default")
      (node (ref "U4") (pin "7") (pinfunction "OUT2_7") (pintype "passive"))
    )
  )
)
